# pecl_pulse_gen.net
KiCad netlist of a schematic drawn in EAGLE
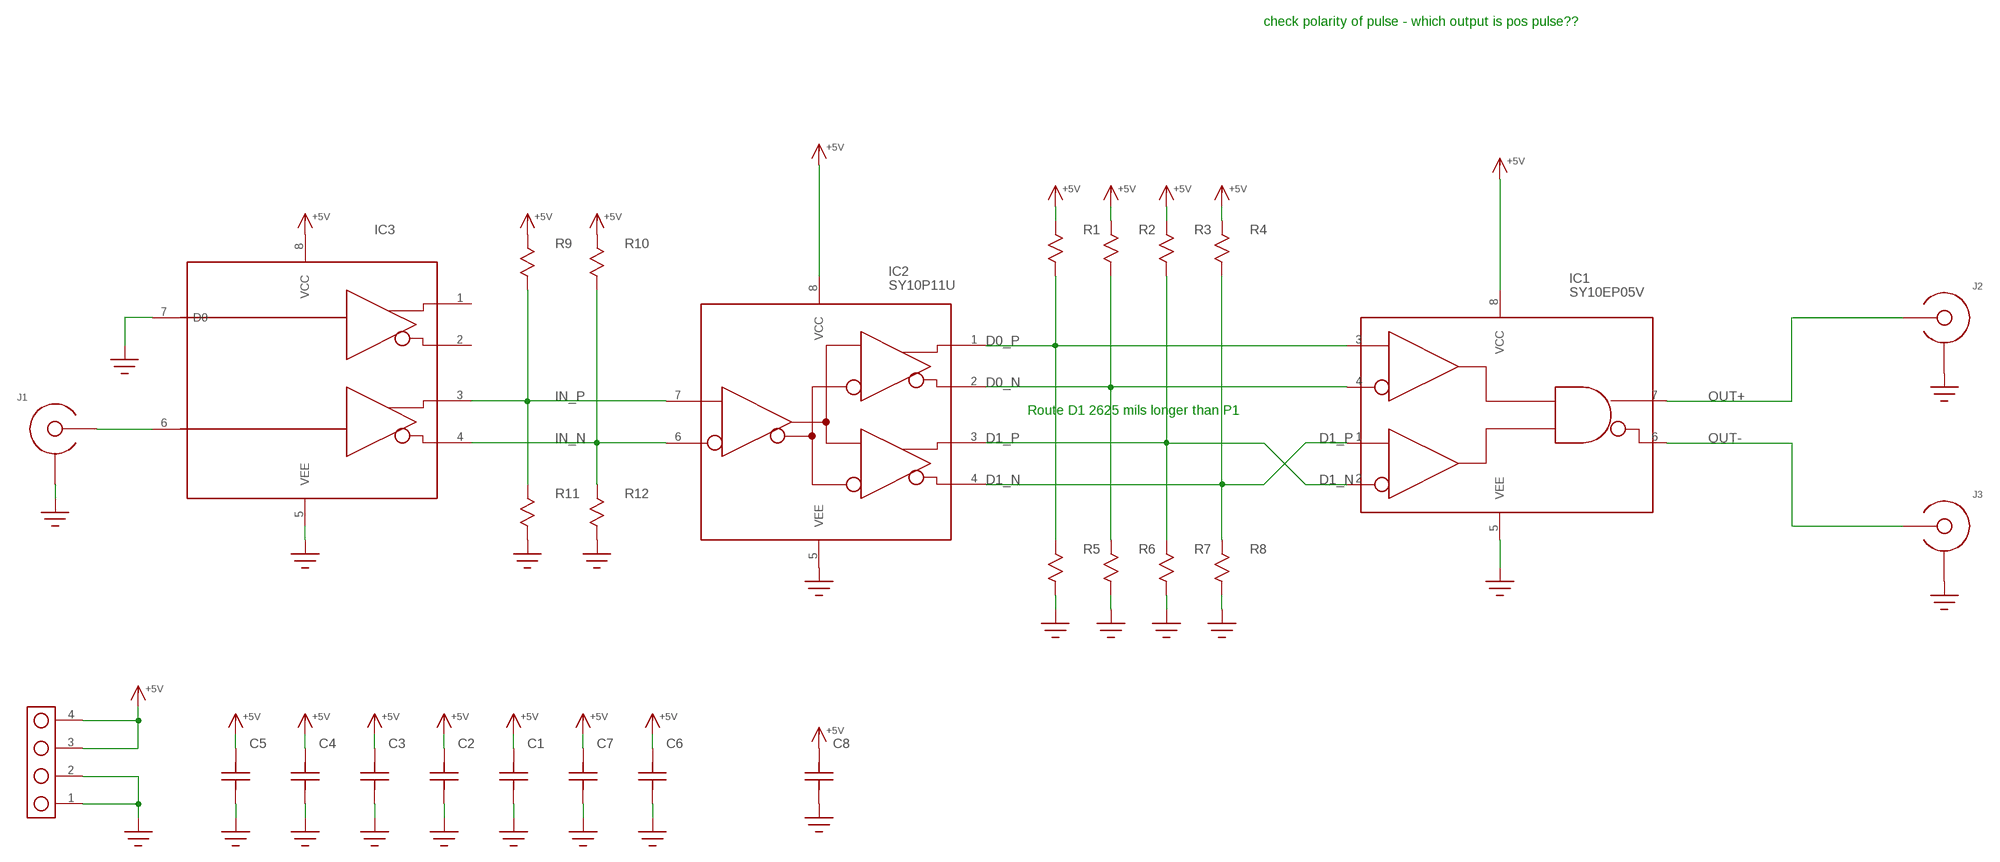
[diagram p0: schematic, sheet 1]

(export (version "E")
  (design (tool "Eeschema 10.0.6"))
  (components
    (comp (ref "C1")
      (value "C0603")
      (footprint "eagle-import:C0603")
      (libsource (lib "eagle-import") (part "C0603"))
    )
    (comp (ref "C2")
      (value "C0603")
      (footprint "eagle-import:C0603")
      (libsource (lib "eagle-import") (part "C0603"))
    )
    (comp (ref "C3")
      (value "C0603")
      (footprint "eagle-import:C0603")
      (libsource (lib "eagle-import") (part "C0603"))
    )
    (comp (ref "C4")
      (value "C0603")
      (footprint "eagle-import:C0603")
      (libsource (lib "eagle-import") (part "C0603"))
    )
    (comp (ref "C5")
      (value "C0603")
      (footprint "eagle-import:C0603")
      (libsource (lib "eagle-import") (part "C0603"))
    )
    (comp (ref "C6")
      (value "C0603")
      (footprint "eagle-import:C0603")
      (libsource (lib "eagle-import") (part "C0603"))
    )
    (comp (ref "C7")
      (value "C0603")
      (footprint "eagle-import:C0603")
      (libsource (lib "eagle-import") (part "C0603"))
    )
    (comp (ref "C8")
      (value "C1206")
      (footprint "eagle-import:1206")
      (libsource (lib "eagle-import") (part "C1206"))
    )
    (comp (ref "IC1")
      (value "SY10EP05V")
      (footprint "eagle-import:SOIC8")
      (libsource (lib "eagle-import") (part "SY10EP05V"))
    )
    (comp (ref "IC2")
      (value "SY10P11U")
      (footprint "eagle-import:SOIC8")
      (libsource (lib "eagle-import") (part "SY10EP11U"))
    )
    (comp (ref "IC3")
      (value "MC100LVELT22")
      (footprint "eagle-import:SOIC8")
      (libsource (lib "eagle-import") (part "MC100LVELT22"))
    )
    (comp (ref "J1")
      (value "EDGE_LAUNCH_JACK")
      (footprint "eagle-import:EDGE_LAUNCH_RF_CON")
      (libsource (lib "eagle-import") (part "EDGE_LAUNCH_JACK"))
    )
    (comp (ref "J2")
      (value "EDGE_LAUNCH_JACK")
      (footprint "eagle-import:EDGE_LAUNCH_RF_CON")
      (libsource (lib "eagle-import") (part "EDGE_LAUNCH_JACK"))
    )
    (comp (ref "J3")
      (value "EDGE_LAUNCH_JACK")
      (footprint "eagle-import:EDGE_LAUNCH_RF_CON")
      (libsource (lib "eagle-import") (part "EDGE_LAUNCH_JACK"))
    )
    (comp (ref "J4")
      (value "HEADER_4PIN")
      (footprint "eagle-import:HEADER_4PIN")
      (libsource (lib "eagle-import") (part "HEADER_4PIN"))
    )
    (comp (ref "R1")
      (value "R0402")
      (footprint "eagle-import:0402")
      (libsource (lib "eagle-import") (part "R0402"))
    )
    (comp (ref "R2")
      (value "R0402")
      (footprint "eagle-import:0402")
      (libsource (lib "eagle-import") (part "R0402"))
    )
    (comp (ref "R3")
      (value "R0402")
      (footprint "eagle-import:0402")
      (libsource (lib "eagle-import") (part "R0402"))
    )
    (comp (ref "R4")
      (value "R0402")
      (footprint "eagle-import:0402")
      (libsource (lib "eagle-import") (part "R0402"))
    )
    (comp (ref "R5")
      (value "R0402")
      (footprint "eagle-import:0402")
      (libsource (lib "eagle-import") (part "R0402"))
    )
    (comp (ref "R6")
      (value "R0402")
      (footprint "eagle-import:0402")
      (libsource (lib "eagle-import") (part "R0402"))
    )
    (comp (ref "R7")
      (value "R0402")
      (footprint "eagle-import:0402")
      (libsource (lib "eagle-import") (part "R0402"))
    )
    (comp (ref "R8")
      (value "R0402")
      (footprint "eagle-import:0402")
      (libsource (lib "eagle-import") (part "R0402"))
    )
    (comp (ref "R9")
      (value "R0402")
      (footprint "eagle-import:0402")
      (libsource (lib "eagle-import") (part "R0402"))
    )
    (comp (ref "R10")
      (value "R0402")
      (footprint "eagle-import:0402")
      (libsource (lib "eagle-import") (part "R0402"))
    )
    (comp (ref "R11")
      (value "R0402")
      (footprint "eagle-import:0402")
      (libsource (lib "eagle-import") (part "R0402"))
    )
    (comp (ref "R12")
      (value "R0402")
      (footprint "eagle-import:0402")
      (libsource (lib "eagle-import") (part "R0402"))
    )
  )
  (nets
    (net (code "1") (name "+5V") (class "Default")
      (node (ref "C1") (pin "P$2") (pinfunction "P$2_P$2") (pintype "bidirectional"))
      (node (ref "C2") (pin "P$2") (pinfunction "P$2_P$2") (pintype "bidirectional"))
      (node (ref "C3") (pin "P$2") (pinfunction "P$2_P$2") (pintype "bidirectional"))
      (node (ref "C4") (pin "P$2") (pinfunction "P$2_P$2") (pintype "bidirectional"))
      (node (ref "C5") (pin "P$2") (pinfunction "P$2_P$2") (pintype "bidirectional"))
      (node (ref "C6") (pin "P$2") (pinfunction "P$2_P$2") (pintype "bidirectional"))
      (node (ref "C7") (pin "P$2") (pinfunction "P$2_P$2") (pintype "bidirectional"))
      (node (ref "C8") (pin "P$2") (pinfunction "P$2_P$2") (pintype "bidirectional"))
      (node (ref "IC1") (pin "8") (pinfunction "VCC_8") (pintype "bidirectional"))
      (node (ref "IC2") (pin "8") (pinfunction "VCC_8") (pintype "bidirectional"))
      (node (ref "IC3") (pin "8") (pinfunction "VCC_8") (pintype "bidirectional"))
      (node (ref "J4") (pin "3") (pinfunction "3_3") (pintype "bidirectional"))
      (node (ref "J4") (pin "4") (pinfunction "4_4") (pintype "bidirectional"))
      (node (ref "R1") (pin "1") (pinfunction "P$3_1") (pintype "bidirectional"))
      (node (ref "R10") (pin "1") (pinfunction "P$3_1") (pintype "bidirectional"))
      (node (ref "R2") (pin "1") (pinfunction "P$3_1") (pintype "bidirectional"))
      (node (ref "R3") (pin "1") (pinfunction "P$3_1") (pintype "bidirectional"))
      (node (ref "R4") (pin "1") (pinfunction "P$3_1") (pintype "bidirectional"))
      (node (ref "R9") (pin "1") (pinfunction "P$3_1") (pintype "bidirectional"))
    )
    (net (code "2") (name "/D0_N") (class "Default")
      (node (ref "IC1") (pin "4") (pinfunction "~{D1}_4") (pintype "bidirectional"))
      (node (ref "IC2") (pin "2") (pinfunction "~{Q0}_2") (pintype "bidirectional"))
      (node (ref "R2") (pin "2") (pinfunction "P$4_2") (pintype "bidirectional"))
      (node (ref "R6") (pin "1") (pinfunction "P$3_1") (pintype "bidirectional"))
    )
    (net (code "3") (name "/D0_P") (class "Default")
      (node (ref "IC1") (pin "3") (pinfunction "D1_3") (pintype "bidirectional"))
      (node (ref "IC2") (pin "1") (pinfunction "Q0_1") (pintype "bidirectional"))
      (node (ref "R1") (pin "2") (pinfunction "P$4_2") (pintype "bidirectional"))
      (node (ref "R5") (pin "1") (pinfunction "P$3_1") (pintype "bidirectional"))
    )
    (net (code "4") (name "/D1_N") (class "Default")
      (node (ref "IC1") (pin "1") (pinfunction "D0_1") (pintype "bidirectional"))
      (node (ref "IC2") (pin "4") (pinfunction "~{Q1}_4") (pintype "bidirectional"))
      (node (ref "R4") (pin "2") (pinfunction "P$4_2") (pintype "bidirectional"))
      (node (ref "R8") (pin "1") (pinfunction "P$3_1") (pintype "bidirectional"))
    )
    (net (code "5") (name "/D1_P") (class "Default")
      (node (ref "IC1") (pin "2") (pinfunction "~{D0}_2") (pintype "bidirectional"))
      (node (ref "IC2") (pin "3") (pinfunction "Q1_3") (pintype "bidirectional"))
      (node (ref "R3") (pin "2") (pinfunction "P$4_2") (pintype "bidirectional"))
      (node (ref "R7") (pin "1") (pinfunction "P$3_1") (pintype "bidirectional"))
    )
    (net (code "6") (name "/IN_N") (class "Default")
      (node (ref "IC2") (pin "6") (pinfunction "~{D}_6") (pintype "bidirectional"))
      (node (ref "IC3") (pin "4") (pinfunction "~{Q1}_4") (pintype "bidirectional"))
      (node (ref "R10") (pin "2") (pinfunction "P$4_2") (pintype "bidirectional"))
      (node (ref "R12") (pin "1") (pinfunction "P$3_1") (pintype "bidirectional"))
    )
    (net (code "7") (name "/IN_P") (class "Default")
      (node (ref "IC2") (pin "7") (pinfunction "D_7") (pintype "bidirectional"))
      (node (ref "IC3") (pin "3") (pinfunction "Q1_3") (pintype "bidirectional"))
      (node (ref "R11") (pin "1") (pinfunction "P$3_1") (pintype "bidirectional"))
      (node (ref "R9") (pin "2") (pinfunction "P$4_2") (pintype "bidirectional"))
    )
    (net (code "8") (name "/OUT+") (class "Default")
      (node (ref "IC1") (pin "7") (pinfunction "Q_7") (pintype "bidirectional"))
      (node (ref "J2") (pin "CENTER") (pinfunction "CENTER_CENTER") (pintype "bidirectional"))
    )
    (net (code "9") (name "/OUT-") (class "Default")
      (node (ref "IC1") (pin "6") (pinfunction "~{Q}_6") (pintype "bidirectional"))
      (node (ref "J3") (pin "CENTER") (pinfunction "CENTER_CENTER") (pintype "bidirectional"))
    )
    (net (code "10") (name "GND") (class "Default")
      (node (ref "C1") (pin "P$1") (pinfunction "P$1_P$1") (pintype "bidirectional"))
      (node (ref "C2") (pin "P$1") (pinfunction "P$1_P$1") (pintype "bidirectional"))
      (node (ref "C3") (pin "P$1") (pinfunction "P$1_P$1") (pintype "bidirectional"))
      (node (ref "C4") (pin "P$1") (pinfunction "P$1_P$1") (pintype "bidirectional"))
      (node (ref "C5") (pin "P$1") (pinfunction "P$1_P$1") (pintype "bidirectional"))
      (node (ref "C6") (pin "P$1") (pinfunction "P$1_P$1") (pintype "bidirectional"))
      (node (ref "C7") (pin "P$1") (pinfunction "P$1_P$1") (pintype "bidirectional"))
      (node (ref "C8") (pin "P$1") (pinfunction "P$1_P$1") (pintype "bidirectional"))
      (node (ref "IC1") (pin "5") (pinfunction "VEE_5") (pintype "bidirectional"))
      (node (ref "IC2") (pin "5") (pinfunction "VEE_5") (pintype "bidirectional"))
      (node (ref "IC3") (pin "5") (pinfunction "VEE_5") (pintype "bidirectional"))
      (node (ref "IC3") (pin "7") (pinfunction "D0_7") (pintype "bidirectional"))
      (node (ref "J1") (pin "GND@1") (pinfunction "SHIELD_GND@1") (pintype "bidirectional"))
      (node (ref "J1") (pin "GND@10") (pinfunction "SHIELD_GND@10") (pintype "bidirectional"))
      (node (ref "J1") (pin "GND@11") (pinfunction "SHIELD_GND@11") (pintype "bidirectional"))
      (node (ref "J1") (pin "GND@12") (pinfunction "SHIELD_GND@12") (pintype "bidirectional"))
      (node (ref "J1") (pin "GND@2") (pinfunction "SHIELD_GND@2") (pintype "bidirectional"))
      (node (ref "J1") (pin "GND@3") (pinfunction "SHIELD_GND@3") (pintype "bidirectional"))
      (node (ref "J1") (pin "GND@4") (pinfunction "SHIELD_GND@4") (pintype "bidirectional"))
      (node (ref "J1") (pin "GND@5") (pinfunction "SHIELD_GND@5") (pintype "bidirectional"))
      (node (ref "J1") (pin "GND@6") (pinfunction "SHIELD_GND@6") (pintype "bidirectional"))
      (node (ref "J1") (pin "GND@7") (pinfunction "SHIELD_GND@7") (pintype "bidirectional"))
      (node (ref "J1") (pin "GND@8") (pinfunction "SHIELD_GND@8") (pintype "bidirectional"))
      (node (ref "J1") (pin "GND@9") (pinfunction "SHIELD_GND@9") (pintype "bidirectional"))
      (node (ref "J1") (pin "SHIELD@1") (pinfunction "SHIELD_SHIELD@1") (pintype "bidirectional"))
      (node (ref "J1") (pin "SHIELD@2") (pinfunction "SHIELD_SHIELD@2") (pintype "bidirectional"))
      (node (ref "J2") (pin "GND@1") (pinfunction "SHIELD_GND@1") (pintype "bidirectional"))
      (node (ref "J2") (pin "GND@10") (pinfunction "SHIELD_GND@10") (pintype "bidirectional"))
      (node (ref "J2") (pin "GND@11") (pinfunction "SHIELD_GND@11") (pintype "bidirectional"))
      (node (ref "J2") (pin "GND@12") (pinfunction "SHIELD_GND@12") (pintype "bidirectional"))
      (node (ref "J2") (pin "GND@2") (pinfunction "SHIELD_GND@2") (pintype "bidirectional"))
      (node (ref "J2") (pin "GND@3") (pinfunction "SHIELD_GND@3") (pintype "bidirectional"))
      (node (ref "J2") (pin "GND@4") (pinfunction "SHIELD_GND@4") (pintype "bidirectional"))
      (node (ref "J2") (pin "GND@5") (pinfunction "SHIELD_GND@5") (pintype "bidirectional"))
      (node (ref "J2") (pin "GND@6") (pinfunction "SHIELD_GND@6") (pintype "bidirectional"))
      (node (ref "J2") (pin "GND@7") (pinfunction "SHIELD_GND@7") (pintype "bidirectional"))
      (node (ref "J2") (pin "GND@8") (pinfunction "SHIELD_GND@8") (pintype "bidirectional"))
      (node (ref "J2") (pin "GND@9") (pinfunction "SHIELD_GND@9") (pintype "bidirectional"))
      (node (ref "J2") (pin "SHIELD@1") (pinfunction "SHIELD_SHIELD@1") (pintype "bidirectional"))
      (node (ref "J2") (pin "SHIELD@2") (pinfunction "SHIELD_SHIELD@2") (pintype "bidirectional"))
      (node (ref "J3") (pin "GND@1") (pinfunction "SHIELD_GND@1") (pintype "bidirectional"))
      (node (ref "J3") (pin "GND@10") (pinfunction "SHIELD_GND@10") (pintype "bidirectional"))
      (node (ref "J3") (pin "GND@11") (pinfunction "SHIELD_GND@11") (pintype "bidirectional"))
      (node (ref "J3") (pin "GND@12") (pinfunction "SHIELD_GND@12") (pintype "bidirectional"))
      (node (ref "J3") (pin "GND@2") (pinfunction "SHIELD_GND@2") (pintype "bidirectional"))
      (node (ref "J3") (pin "GND@3") (pinfunction "SHIELD_GND@3") (pintype "bidirectional"))
      (node (ref "J3") (pin "GND@4") (pinfunction "SHIELD_GND@4") (pintype "bidirectional"))
      (node (ref "J3") (pin "GND@5") (pinfunction "SHIELD_GND@5") (pintype "bidirectional"))
      (node (ref "J3") (pin "GND@6") (pinfunction "SHIELD_GND@6") (pintype "bidirectional"))
      (node (ref "J3") (pin "GND@7") (pinfunction "SHIELD_GND@7") (pintype "bidirectional"))
      (node (ref "J3") (pin "GND@8") (pinfunction "SHIELD_GND@8") (pintype "bidirectional"))
      (node (ref "J3") (pin "GND@9") (pinfunction "SHIELD_GND@9") (pintype "bidirectional"))
      (node (ref "J3") (pin "SHIELD@1") (pinfunction "SHIELD_SHIELD@1") (pintype "bidirectional"))
      (node (ref "J3") (pin "SHIELD@2") (pinfunction "SHIELD_SHIELD@2") (pintype "bidirectional"))
      (node (ref "J4") (pin "1") (pinfunction "1_1") (pintype "bidirectional"))
      (node (ref "J4") (pin "2") (pinfunction "2_2") (pintype "bidirectional"))
      (node (ref "R11") (pin "2") (pinfunction "P$4_2") (pintype "bidirectional"))
      (node (ref "R12") (pin "2") (pinfunction "P$4_2") (pintype "bidirectional"))
      (node (ref "R5") (pin "2") (pinfunction "P$4_2") (pintype "bidirectional"))
      (node (ref "R6") (pin "2") (pinfunction "P$4_2") (pintype "bidirectional"))
      (node (ref "R7") (pin "2") (pinfunction "P$4_2") (pintype "bidirectional"))
      (node (ref "R8") (pin "2") (pinfunction "P$4_2") (pintype "bidirectional"))
    )
    (net (code "11") (name "Net-(IC3-D1)") (class "Default")
      (node (ref "IC3") (pin "6") (pinfunction "D1_6") (pintype "bidirectional"))
      (node (ref "J1") (pin "CENTER") (pinfunction "CENTER_CENTER") (pintype "bidirectional"))
    )
    (net (code "12") (name "unconnected-(IC3-Q0-Pad1)") (class "Default")
      (node (ref "IC3") (pin "1") (pinfunction "Q0_1") (pintype "bidirectional"))
    )
    (net (code "13") (name "unconnected-(IC3-~{Q0}-Pad2)") (class "Default")
      (node (ref "IC3") (pin "2") (pinfunction "~{Q0}_2") (pintype "bidirectional"))
    )
  )
)
